# Sensors_CAN.net
KiCad netlist of a schematic drawn in Altium Designer
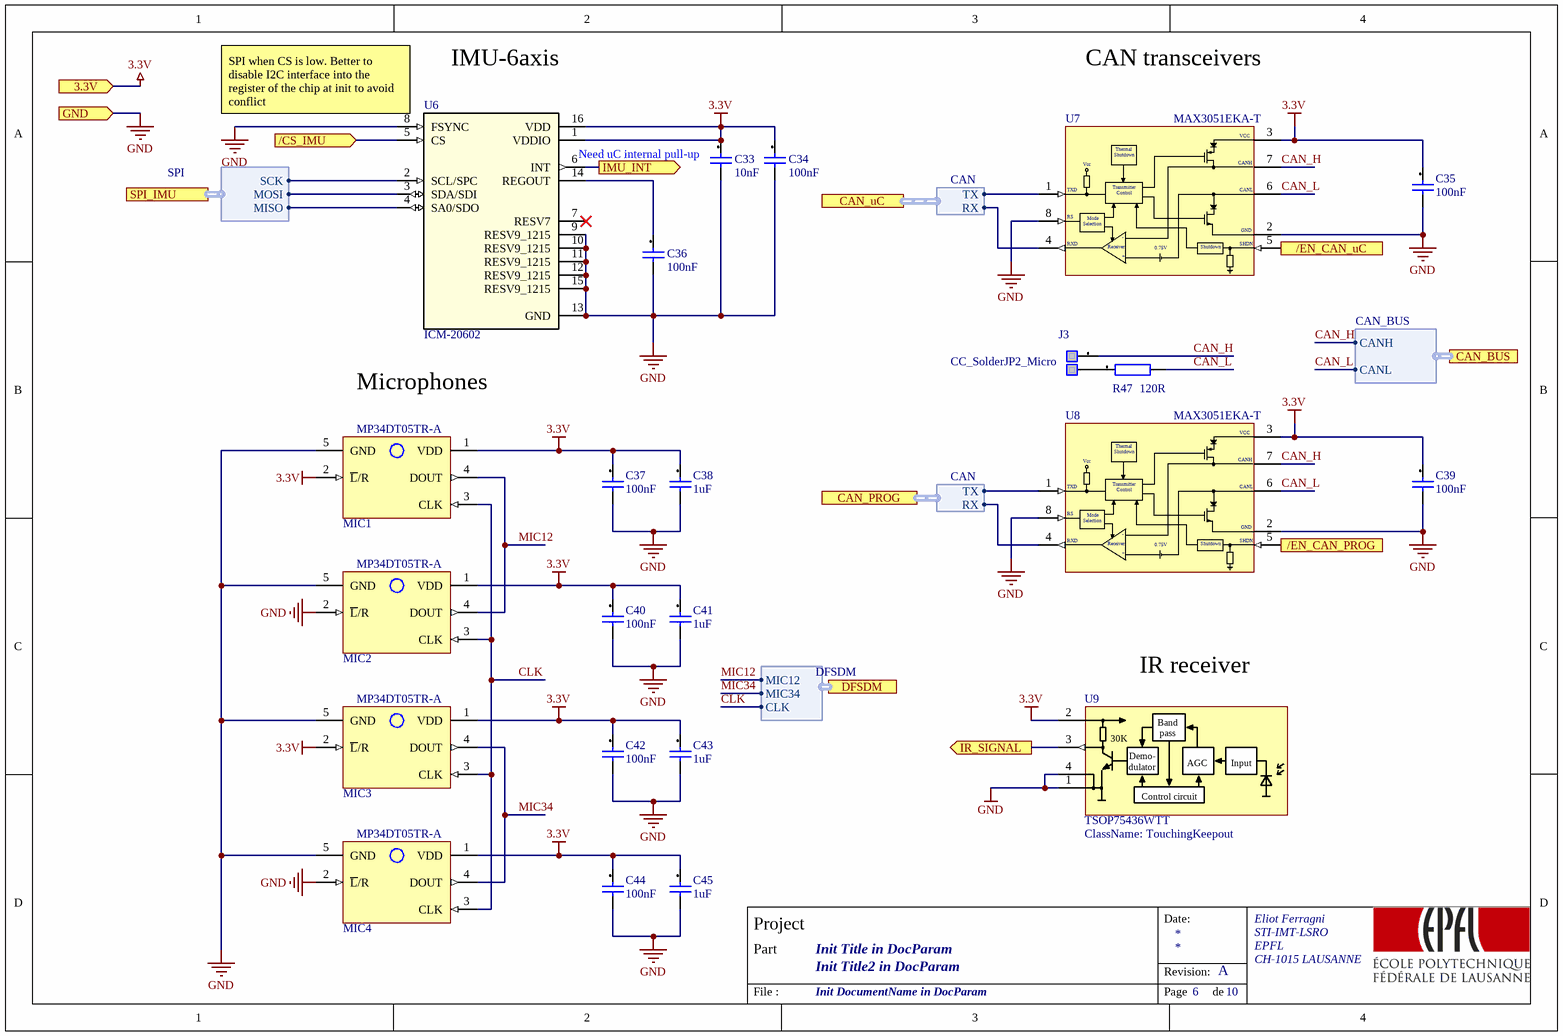
[diagram p0: Sensors + CAN.SchDoc]

(export (version "E")
  (design (tool "Eeschema 10.0.6"))
  (components
    (comp (ref "C33")
      (value "10nF")
      (footprint "CAPC0201(0603)33_L")
      (description "Capacitor TBD 0201")
      (libsource (lib "LSRO1Altium") (part "CAP-NP"))
    )
    (comp (ref "C34")
      (value "100nF")
      (footprint "CAPC0201(0603)33_L")
      (description "Capacitor TBD 0201")
      (libsource (lib "LSRO1Altium") (part "CAP-NP"))
    )
    (comp (ref "C35")
      (value "100nF")
      (footprint "CAPC0201(0603)33_L")
      (description "Capacitor TBD 0201")
      (libsource (lib "LSRO1Altium") (part "CAP-NP"))
    )
    (comp (ref "C36")
      (value "100nF")
      (footprint "CAPC0201(0603)33_L")
      (description "Capacitor TBD 0201")
      (libsource (lib "LSRO1Altium") (part "CAP-NP"))
    )
    (comp (ref "C37")
      (value "100nF")
      (footprint "CAPC0201(0603)33_L")
      (description "Capacitor TBD 0201")
      (libsource (lib "LSRO1Altium") (part "CAP-NP"))
    )
    (comp (ref "C38")
      (value "1uF")
      (footprint "CAPC0201(0603)33_L")
      (description "Capacitor TBD 0201")
      (libsource (lib "LSRO1Altium") (part "CAP-NP"))
    )
    (comp (ref "C39")
      (value "100nF")
      (footprint "CAPC0201(0603)33_L")
      (description "Capacitor TBD 0201")
      (libsource (lib "LSRO1Altium") (part "CAP-NP"))
    )
    (comp (ref "C40")
      (value "100nF")
      (footprint "CAPC0201(0603)33_L")
      (description "Capacitor TBD 0201")
      (libsource (lib "LSRO1Altium") (part "CAP-NP"))
    )
    (comp (ref "C41")
      (value "1uF")
      (footprint "CAPC0201(0603)33_L")
      (description "Capacitor TBD 0201")
      (libsource (lib "LSRO1Altium") (part "CAP-NP"))
    )
    (comp (ref "C42")
      (value "100nF")
      (footprint "CAPC0201(0603)33_L")
      (description "Capacitor TBD 0201")
      (libsource (lib "LSRO1Altium") (part "CAP-NP"))
    )
    (comp (ref "C43")
      (value "1uF")
      (footprint "CAPC0201(0603)33_L")
      (description "Capacitor TBD 0201")
      (libsource (lib "LSRO1Altium") (part "CAP-NP"))
    )
    (comp (ref "C44")
      (value "100nF")
      (footprint "CAPC0201(0603)33_L")
      (description "Capacitor TBD 0201")
      (libsource (lib "LSRO1Altium") (part "CAP-NP"))
    )
    (comp (ref "C45")
      (value "1uF")
      (footprint "CAPC0201(0603)33_L")
      (description "Capacitor TBD 0201")
      (libsource (lib "LSRO1Altium") (part "CAP-NP"))
    )
    (comp (ref "J3")
      (value "CC_SolderJP2_Micro")
      (footprint "CC_SolderJP_U")
      (description "Micro Solder Jumper 2 leads")
      (libsource (lib "LSRO1Altium") (part "SolderJP2"))
    )
    (comp (ref "MIC1")
      (value "MP34DT05TR-A")
      (footprint "MIC-PACK_MP34DT05-A(Primary)")
      (description "MEMS AUD MIC SENSOR OMNI 4HCLGA")
      (fields (field (name "MANUFACTURER") "STMicroelectronics"))
      (libsource (lib "Schlib") (part "MP34DT05TR-A"))
    )
    (comp (ref "MIC2")
      (value "MP34DT05TR-A")
      (footprint "MIC-PACK_MP34DT05-A(Primary)")
      (description "MEMS AUD MIC SENSOR OMNI 4HCLGA")
      (fields (field (name "MANUFACTURER") "STMicroelectronics"))
      (libsource (lib "Schlib") (part "MP34DT05TR-A"))
    )
    (comp (ref "MIC3")
      (value "MP34DT05TR-A")
      (footprint "MIC-PACK_MP34DT05-A(Primary)")
      (description "MEMS AUD MIC SENSOR OMNI 4HCLGA")
      (fields (field (name "MANUFACTURER") "STMicroelectronics"))
      (libsource (lib "Schlib") (part "MP34DT05TR-A"))
    )
    (comp (ref "MIC4")
      (value "MP34DT05TR-A")
      (footprint "MIC-PACK_MP34DT05-A(Primary)")
      (description "MEMS AUD MIC SENSOR OMNI 4HCLGA")
      (fields (field (name "MANUFACTURER") "STMicroelectronics"))
      (libsource (lib "Schlib") (part "MP34DT05TR-A"))
    )
    (comp (ref "R47")
      (value "120R")
      (footprint "RESC0201(0603)_L")
      (description "Resistor ToDo 0201")
      (libsource (lib "LSRO1Altium") (part "RES"))
    )
    (comp (ref "U6")
      (value "ICM-20602")
      (footprint "PQFN50P300X300X80-16N")
      (description "IMU ACCEL/GYRO/TEMP I2C/SPI LGA")
      (fields (field (name "MF") "TDK-InvenSense") (field (name "DIGI-KEY_PART_NUMBER") "1428-1060-1-ND"))
      (libsource (lib "Schlib") (part "ICM-20602"))
    )
    (comp (ref "U7")
      (value "MAX3051EKA-T")
      (footprint "SOT23-8")
      (description "+3.3V, 1Mbps, Low-Supply-Current CAN Transceiver")
      (fields (field (name "MANUFACTURER") "Maxim"))
      (libsource (lib "LSRO1Altium") (part "MAX3051"))
    )
    (comp (ref "U8")
      (value "MAX3051EKA-T")
      (footprint "SOT23-8")
      (description "+3.3V, 1Mbps, Low-Supply-Current CAN Transceiver")
      (fields (field (name "MANUFACTURER") "Maxim"))
      (libsource (lib "LSRO1Altium") (part "MAX3051"))
    )
    (comp (ref "U9")
      (value "TSOP75436WTT")
      (footprint "VISHAY-TSOP752-754")
      (description "Vishay 	TSOP75436WTT IR Receiver Modules for Remote Control Systems")
      (fields (field (name "MANUFACTURER") "Vishay") (field (name "CLASSNAME") "TouchingKeepout"))
      (libsource (lib "Schlib") (part "TSOP752-754"))
    )
  )
  (nets
    (net (code "5") (name "/CAN_H") (class "Default")
      (node (ref "J3") (pin "1") (pintype "passive"))
      (node (ref "U7") (pin "7") (pinfunction "CANH_7") (pintype "passive"))
      (node (ref "U8") (pin "7") (pinfunction "CANH_7") (pintype "passive"))
    )
    (net (code "6") (name "/CAN_L") (class "Default")
      (node (ref "R47") (pin "2") (pinfunction "2_2") (pintype "passive"))
      (node (ref "U7") (pin "6") (pinfunction "CANL_6") (pintype "passive"))
      (node (ref "U8") (pin "6") (pinfunction "CANL_6") (pintype "passive"))
    )
    (net (code "7") (name "/CLK") (class "Default")
      (node (ref "MIC1") (pin "3") (pinfunction "CLK_3") (pintype "input"))
      (node (ref "MIC2") (pin "3") (pinfunction "CLK_3") (pintype "input"))
      (node (ref "MIC3") (pin "3") (pinfunction "CLK_3") (pintype "input"))
      (node (ref "MIC4") (pin "3") (pinfunction "CLK_3") (pintype "input"))
    )
    (net (code "8") (name "/IMU_INT") (class "Default")
      (node (ref "U6") (pin "6") (pinfunction "INT_6") (pintype "output"))
    )
    (net (code "9") (name "/IR_SIGNAL") (class "Default")
      (node (ref "U9") (pin "3") (pinfunction "OUT_3") (pintype "output"))
    )
    (net (code "10") (name "/MIC12") (class "Default")
      (node (ref "MIC1") (pin "4") (pinfunction "DOUT_4") (pintype "output"))
      (node (ref "MIC2") (pin "4") (pinfunction "DOUT_4") (pintype "output"))
    )
    (net (code "11") (name "/MIC34") (class "Default")
      (node (ref "MIC3") (pin "4") (pinfunction "DOUT_4") (pintype "output"))
      (node (ref "MIC4") (pin "4") (pinfunction "DOUT_4") (pintype "output"))
    )
    (net (code "16") (name "/{slash}CS_IMU") (class "Default")
      (node (ref "U6") (pin "5") (pinfunction "CS_5") (pintype "input"))
    )
    (net (code "19") (name "/{slash}EN_CAN_PROG") (class "Default")
      (node (ref "U8") (pin "5") (pinfunction "SHDN_5") (pintype "input"))
    )
    (net (code "20") (name "/{slash}EN_CAN_uC") (class "Default")
      (node (ref "U7") (pin "5") (pinfunction "SHDN_5") (pintype "input"))
    )
    (net (code "21") (name "3.3V") (class "Default")
      (node (ref "C33") (pin "1") (pinfunction "1_1") (pintype "passive"))
      (node (ref "C34") (pin "1") (pinfunction "1_1") (pintype "passive"))
      (node (ref "C35") (pin "1") (pinfunction "1_1") (pintype "passive"))
      (node (ref "C37") (pin "1") (pinfunction "1_1") (pintype "passive"))
      (node (ref "C38") (pin "1") (pinfunction "1_1") (pintype "passive"))
      (node (ref "C39") (pin "1") (pinfunction "1_1") (pintype "passive"))
      (node (ref "C40") (pin "1") (pinfunction "1_1") (pintype "passive"))
      (node (ref "C41") (pin "1") (pinfunction "1_1") (pintype "passive"))
      (node (ref "C42") (pin "1") (pinfunction "1_1") (pintype "passive"))
      (node (ref "C43") (pin "1") (pinfunction "1_1") (pintype "passive"))
      (node (ref "C44") (pin "1") (pinfunction "1_1") (pintype "passive"))
      (node (ref "C45") (pin "1") (pinfunction "1_1") (pintype "passive"))
      (node (ref "MIC1") (pin "1") (pinfunction "VDD_1") (pintype "power_in"))
      (node (ref "MIC1") (pin "2") (pinfunction "~{L}/R_2") (pintype "input"))
      (node (ref "MIC2") (pin "1") (pinfunction "VDD_1") (pintype "power_in"))
      (node (ref "MIC3") (pin "1") (pinfunction "VDD_1") (pintype "power_in"))
      (node (ref "MIC3") (pin "2") (pinfunction "~{L}/R_2") (pintype "input"))
      (node (ref "MIC4") (pin "1") (pinfunction "VDD_1") (pintype "power_in"))
      (node (ref "U6") (pin "1") (pinfunction "VDDIO_1") (pintype "power_in"))
      (node (ref "U6") (pin "16") (pinfunction "VDD_16") (pintype "power_in"))
      (node (ref "U7") (pin "3") (pinfunction "VCC_3") (pintype "power_in"))
      (node (ref "U8") (pin "3") (pinfunction "VCC_3") (pintype "power_in"))
      (node (ref "U9") (pin "2") (pinfunction "VS_2") (pintype "power_in"))
    )
    (net (code "22") (name "GND") (class "Default")
      (node (ref "C33") (pin "2") (pinfunction "2_2") (pintype "passive"))
      (node (ref "C34") (pin "2") (pinfunction "2_2") (pintype "passive"))
      (node (ref "C35") (pin "2") (pinfunction "2_2") (pintype "passive"))
      (node (ref "C36") (pin "2") (pinfunction "2_2") (pintype "passive"))
      (node (ref "C37") (pin "2") (pinfunction "2_2") (pintype "passive"))
      (node (ref "C38") (pin "2") (pinfunction "2_2") (pintype "passive"))
      (node (ref "C39") (pin "2") (pinfunction "2_2") (pintype "passive"))
      (node (ref "C40") (pin "2") (pinfunction "2_2") (pintype "passive"))
      (node (ref "C41") (pin "2") (pinfunction "2_2") (pintype "passive"))
      (node (ref "C42") (pin "2") (pinfunction "2_2") (pintype "passive"))
      (node (ref "C43") (pin "2") (pinfunction "2_2") (pintype "passive"))
      (node (ref "C44") (pin "2") (pinfunction "2_2") (pintype "passive"))
      (node (ref "C45") (pin "2") (pinfunction "2_2") (pintype "passive"))
      (node (ref "MIC1") (pin "5") (pinfunction "GND_5") (pintype "power_in"))
      (node (ref "MIC2") (pin "2") (pinfunction "~{L}/R_2") (pintype "input"))
      (node (ref "MIC2") (pin "5") (pinfunction "GND_5") (pintype "power_in"))
      (node (ref "MIC3") (pin "5") (pinfunction "GND_5") (pintype "power_in"))
      (node (ref "MIC4") (pin "2") (pinfunction "~{L}/R_2") (pintype "input"))
      (node (ref "MIC4") (pin "5") (pinfunction "GND_5") (pintype "power_in"))
      (node (ref "U6") (pin "10") (pinfunction "RESV9_1215_10") (pintype "passive"))
      (node (ref "U6") (pin "11") (pinfunction "RESV9_1215_11") (pintype "passive"))
      (node (ref "U6") (pin "12") (pinfunction "RESV9_1215_12") (pintype "passive"))
      (node (ref "U6") (pin "13") (pinfunction "GND_13") (pintype "power_in"))
      (node (ref "U6") (pin "15") (pinfunction "RESV9_1215_15") (pintype "passive"))
      (node (ref "U6") (pin "8") (pinfunction "FSYNC_8") (pintype "input"))
      (node (ref "U6") (pin "9") (pinfunction "RESV9_1215_9") (pintype "passive"))
      (node (ref "U7") (pin "2") (pinfunction "GND_2") (pintype "power_in"))
      (node (ref "U7") (pin "8") (pinfunction "RS_8") (pintype "input"))
      (node (ref "U8") (pin "2") (pinfunction "GND_2") (pintype "power_in"))
      (node (ref "U8") (pin "8") (pinfunction "RS_8") (pintype "input"))
      (node (ref "U9") (pin "1") (pinfunction "GND_1") (pintype "power_in"))
      (node (ref "U9") (pin "4") (pinfunction "GND_4") (pintype "power_in"))
    )
    (net (code "23") (name "Net-(J3-Pad2)") (class "Default")
      (node (ref "J3") (pin "2") (pintype "passive"))
      (node (ref "R47") (pin "1") (pinfunction "1_1") (pintype "passive"))
    )
    (net (code "24") (name "Net-(U6-REGOUT)") (class "Default")
      (node (ref "C36") (pin "1") (pinfunction "1_1") (pintype "passive"))
      (node (ref "U6") (pin "14") (pinfunction "REGOUT_14") (pintype "passive"))
    )
    (net (code "25") (name "unconnected-(U6-RESV7-Pad7)") (class "Default")
      (node (ref "U6") (pin "7") (pinfunction "RESV7_7") (pintype "passive+no_connect"))
    )
    (net (code "26") (name "unconnected-(U6-SA0{slash}SDO-Pad4)") (class "Default")
      (node (ref "U6") (pin "4") (pinfunction "SA0/SDO_4") (pintype "bidirectional"))
    )
    (net (code "27") (name "unconnected-(U6-SCL{slash}SPC-Pad2)") (class "Default")
      (node (ref "U6") (pin "2") (pinfunction "SCL/SPC_2") (pintype "input"))
    )
    (net (code "28") (name "unconnected-(U6-SDA{slash}SDI-Pad3)") (class "Default")
      (node (ref "U6") (pin "3") (pinfunction "SDA/SDI_3") (pintype "bidirectional"))
    )
    (net (code "29") (name "unconnected-(U7-RXD-Pad4)") (class "Default")
      (node (ref "U7") (pin "4") (pinfunction "RXD_4") (pintype "output"))
    )
    (net (code "30") (name "unconnected-(U7-TXD-Pad1)") (class "Default")
      (node (ref "U7") (pin "1") (pinfunction "TXD_1") (pintype "input"))
    )
    (net (code "31") (name "unconnected-(U8-RXD-Pad4)") (class "Default")
      (node (ref "U8") (pin "4") (pinfunction "RXD_4") (pintype "output"))
    )
    (net (code "32") (name "unconnected-(U8-TXD-Pad1)") (class "Default")
      (node (ref "U8") (pin "1") (pinfunction "TXD_1") (pintype "input"))
    )
  )
)
